# PWR_MCU.net
KiCad netlist of a schematic drawn in Altium Designer
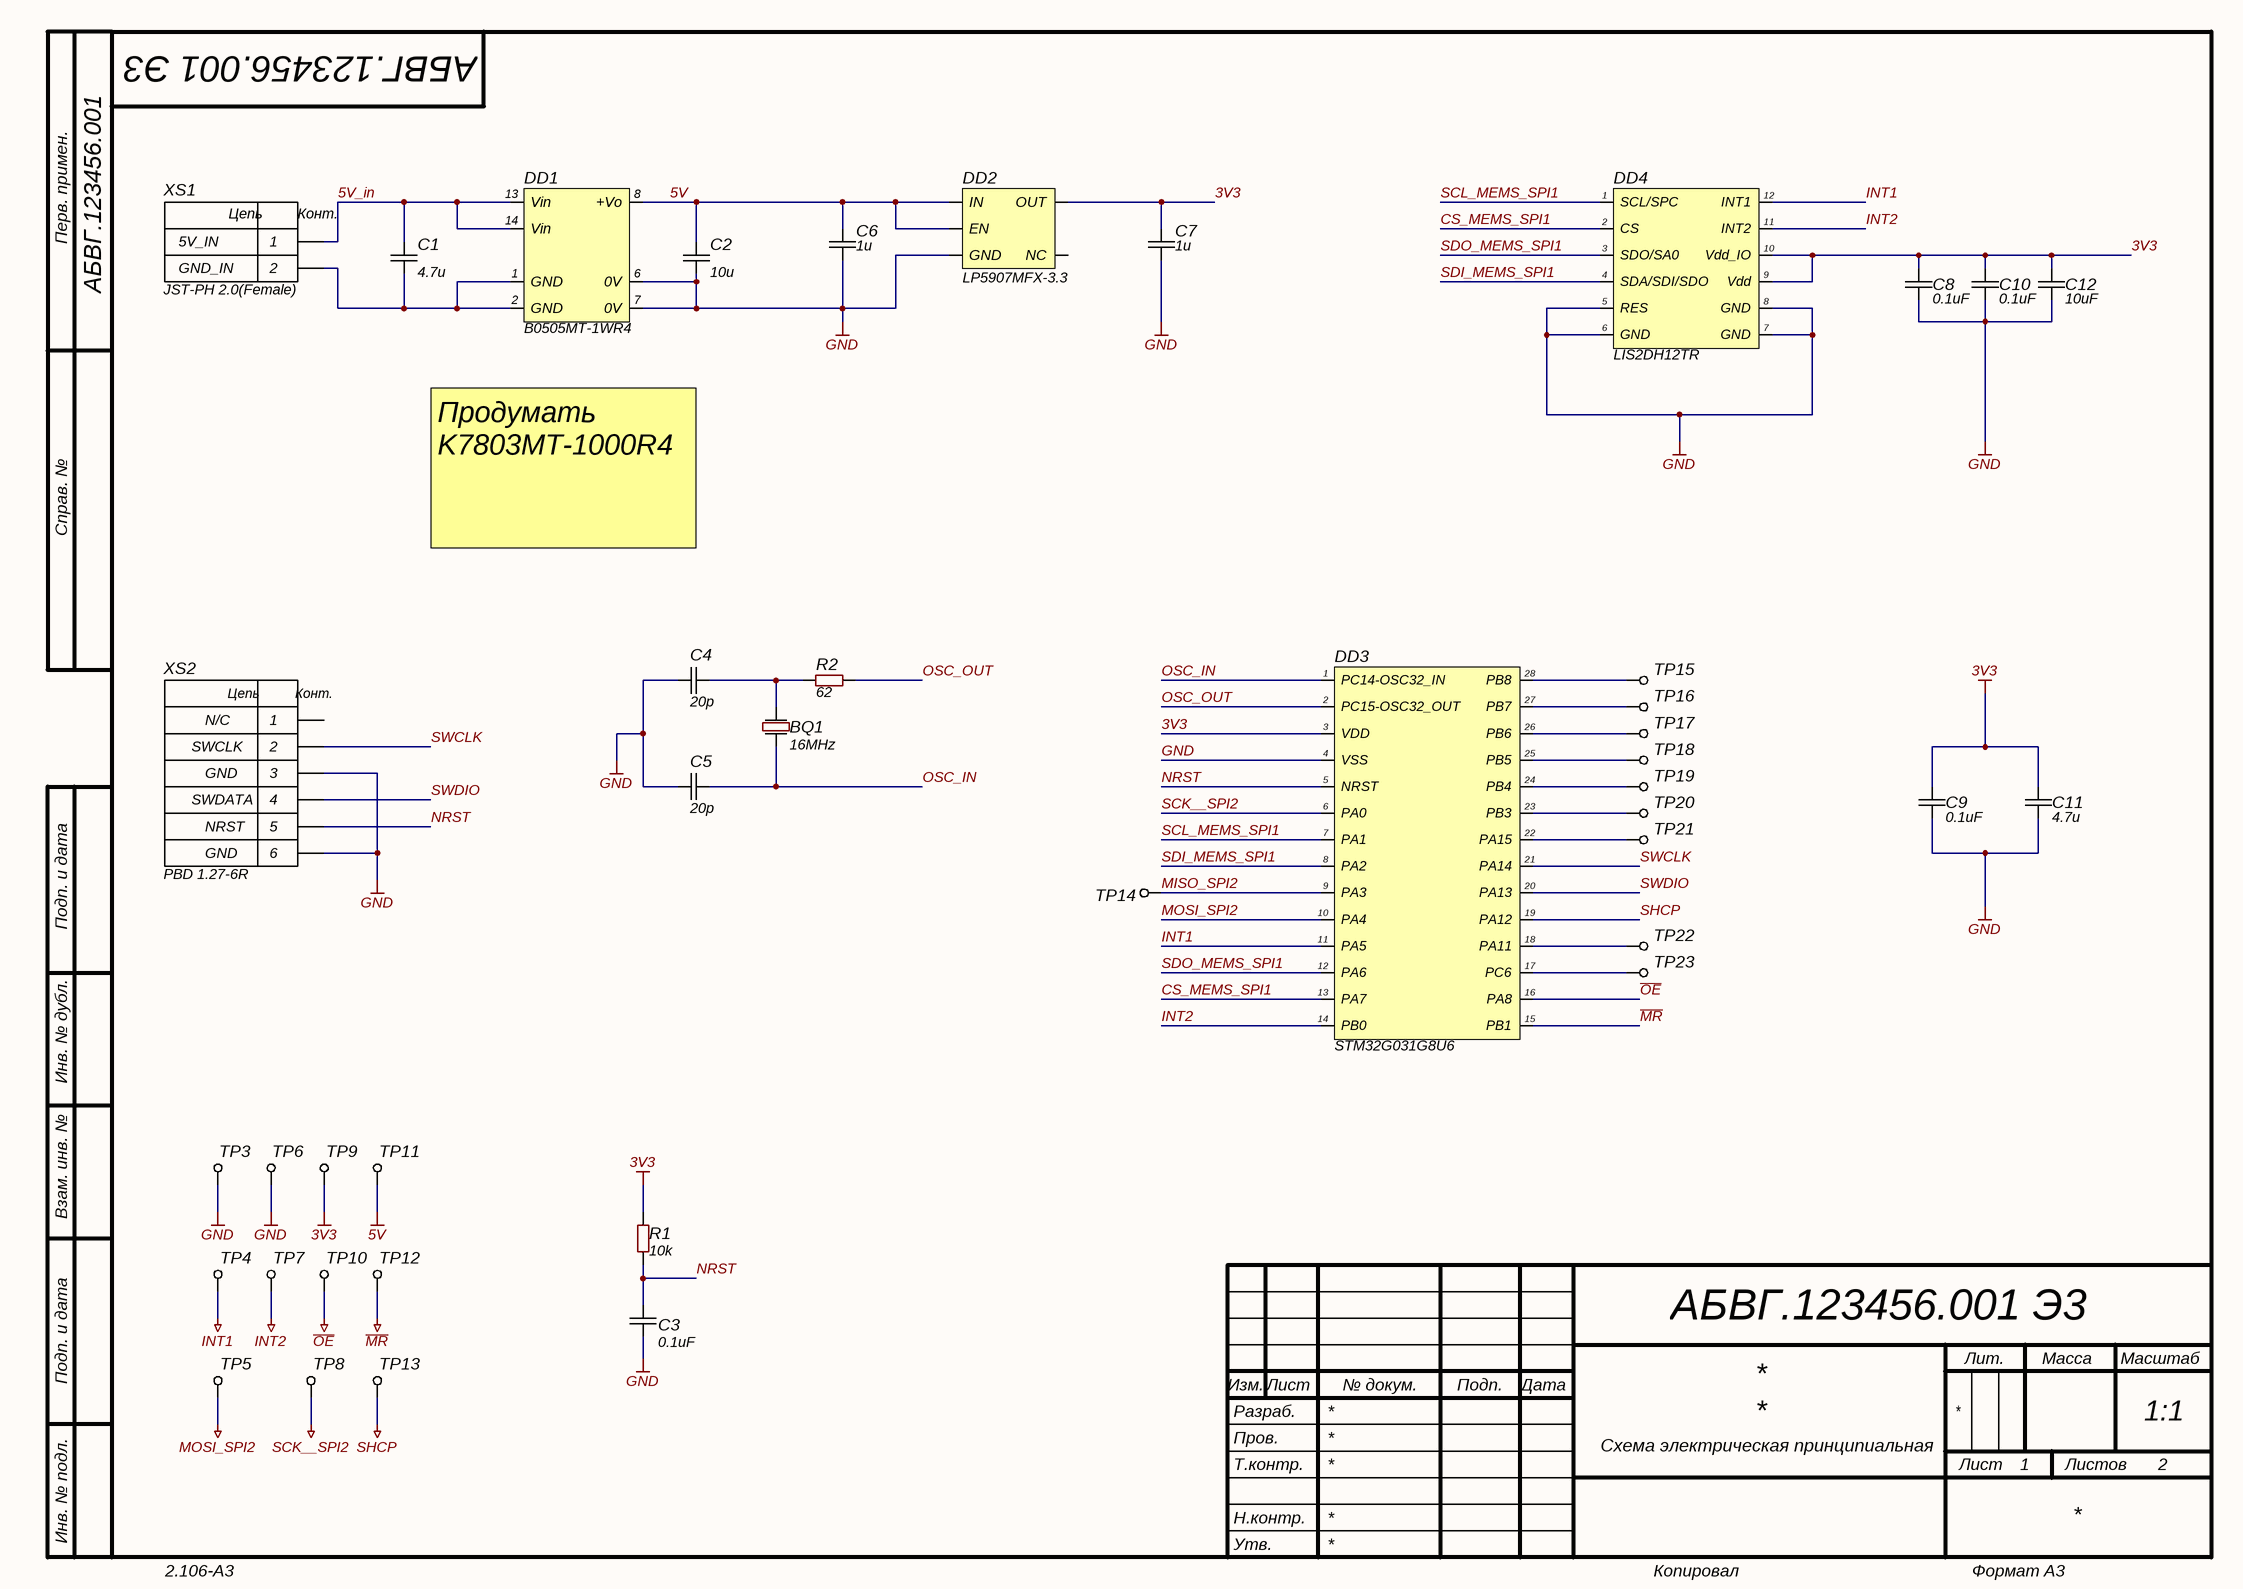
[diagram p0: PWR_MCU.SchDoc]

(export (version "E")
  (design (tool "Eeschema 10.0.6"))
  (components
    (comp (ref "BQ1")
      (value "SMD3225-16.000MHz")
      (footprint "OSC: 3225")
      (description "Resonator")
      (fields
        (field (name "MANUFACTURER") "Diodes Incorporated")
        (field (name "PARTNUMBER") "FL1000002")
        (field (name "FREQUENCY") "16MHz")
      )
      (libsource (lib "oscilator") (part "Crystal_3225"))
    )
    (comp (ref "C1")
      (value "4.7u")
      (footprint "CAP: 0805")
      (fields
        (field (name "MANUFACTURER") "Yageo")
        (field (name "PARTNUMBER") "CC0805KRX7R7BB104")
        (field (name "VALUEMANUFACTURERPARTNUMBER") "Ceramic capacitor, 4.7u, X7R, ±10%, 50V, 0805, -55...+125°C")
      )
      (libsource (lib "capacitor") (part "Ceramic_0805"))
    )
    (comp (ref "C2")
      (value "10u")
      (footprint "CAP: 0805")
      (fields
        (field (name "MANUFACTURER") "Yageo")
        (field (name "PARTNUMBER") "CC0805KRX7R7BB104")
        (field (name "VALUEMANUFACTURERPARTNUMBER") "Ceramic capacitor, 10u, X7R, ±10%, 50V, 0805, -55...+125°C")
      )
      (libsource (lib "capacitor") (part "Ceramic_0805"))
    )
    (comp (ref "C3")
      (value "0.1uF")
      (footprint "CAP: 0603")
      (fields
        (field (name "MANUFACTURER") "Yageo")
        (field (name "PARTNUMBER") "CC0603KRX7R7BB104")
        (field (name "VALUEMANUFACTURERPARTNUMBER") "Ceramic capacitor, 0.1uF, X7R, ±10%, 16V, 0603, -55...+125°C")
      )
      (libsource (lib "capacitor") (part "Ceramic_0603"))
    )
    (comp (ref "C4")
      (value "20p")
      (footprint "CAP: 0603")
      (description "Capacitor")
      (fields (field (name "MANUFACTURER") "Yageo") (field (name "PARTNUMBER") "CC0603KRX7R7BB104"))
      (libsource (lib "capacitor") (part "Ceramic_0603"))
    )
    (comp (ref "C5")
      (value "20p")
      (footprint "CAP: 0603")
      (description "Capacitor")
      (fields (field (name "MANUFACTURER") "Yageo") (field (name "PARTNUMBER") "CC0603KRX7R7BB104"))
      (libsource (lib "capacitor") (part "Ceramic_0603"))
    )
    (comp (ref "C6")
      (value "1u")
      (footprint "CAP: 0603")
      (description "Capacitor")
      (fields (field (name "MANUFACTURER") "Yageo") (field (name "PARTNUMBER") "CC0603KRX7R7BB104"))
      (libsource (lib "capacitor") (part "Ceramic_0603"))
    )
    (comp (ref "C7")
      (value "1u")
      (footprint "CAP: 0603")
      (description "Capacitor")
      (fields (field (name "MANUFACTURER") "Yageo") (field (name "PARTNUMBER") "CC0603KRX7R7BB104"))
      (libsource (lib "capacitor") (part "Ceramic_0603"))
    )
    (comp (ref "C8")
      (value "0.1uF")
      (footprint "CAP: 0603")
      (fields
        (field (name "MANUFACTURER") "Yageo")
        (field (name "PARTNUMBER") "CC0603KRX7R7BB104")
        (field (name "VALUEMANUFACTURERPARTNUMBER") "Ceramic capacitor, 0.1uF, X7R, ±10%, 16V, 0603, -55...+125°C")
      )
      (libsource (lib "capacitor") (part "Ceramic_0603"))
    )
    (comp (ref "C9")
      (value "0.1uF")
      (footprint "CAP: 0603")
      (fields
        (field (name "MANUFACTURER") "Yageo")
        (field (name "PARTNUMBER") "CC0603KRX7R7BB104")
        (field (name "VALUEMANUFACTURERPARTNUMBER") "Ceramic capacitor, 0.1uF, X7R, ±10%, 16V, 0603, -55...+125°C")
      )
      (libsource (lib "capacitor") (part "Ceramic_0603"))
    )
    (comp (ref "C10")
      (value "0.1uF")
      (footprint "CAP: 0603")
      (fields
        (field (name "MANUFACTURER") "Yageo")
        (field (name "PARTNUMBER") "CC0603KRX7R7BB104")
        (field (name "VALUEMANUFACTURERPARTNUMBER") "Ceramic capacitor, 0.1uF, X7R, ±10%, 16V, 0603, -55...+125°C")
      )
      (libsource (lib "capacitor") (part "Ceramic_0603"))
    )
    (comp (ref "C11")
      (value "4.7u")
      (footprint "CAP: 0603")
      (fields
        (field (name "MANUFACTURER") "Yageo")
        (field (name "PARTNUMBER") "CC0603KRX7R7BB104")
        (field (name "VALUEMANUFACTURERPARTNUMBER") "Ceramic capacitor, 4.7u, X7R, ±10%, 16V, 0603, -55...+125°C")
      )
      (libsource (lib "capacitor") (part "Ceramic_0603"))
    )
    (comp (ref "C12")
      (value "10uF")
      (footprint "CAP: 0603")
      (fields
        (field (name "MANUFACTURER") "Yageo")
        (field (name "PARTNUMBER") "CC0603KRX7R7BB104")
        (field (name "VALUEMANUFACTURERPARTNUMBER") "Ceramic capacitor, 10uF, X7R, ±10%, 16V, 0603, -55...+125°C")
      )
      (libsource (lib "capacitor") (part "Ceramic_0603"))
    )
    (comp (ref "DD1")
      (value "B0505MT-1WR4")
      (footprint "B0505MT-1WR4")
      (description "Isolated DC-DC converter")
      (libsource (lib "ic-power-supply") (part "B0505MT-1WR4"))
    )
    (comp (ref "DD2")
      (value "LP5907MFX-3.3")
      (footprint "SOT23-5")
      (description "LDO")
      (libsource (lib "ic-power-supply") (part "LP5907MFX-3.3"))
    )
    (comp (ref "DD3")
      (value "STM32G031G8U6")
      (footprint "28-UFQFPN")
      (description "Cortex-M0+")
      (libsource (lib "ic-mcu") (part "STM32G031G8U6"))
    )
    (comp (ref "DD4")
      (value "LIS2DH12TR")
      (footprint "12-LGA")
      (description "MEMS accelerometer")
      (libsource (lib "electromechanics") (part "LIS2DH12TR"))
    )
    (comp (ref "R1")
      (value "10k")
      (footprint "RES: 0603")
      (fields
        (field (name "MANUFACTURER") "Yageo")
        (field (name "PARTNUMBER") "RC0603JR-07100RL")
        (field (name "VALUEMANUFACTURERPARTNUMBER") "Resistor film, 10k, , 0603, 0.1W, -55...+125°C")
      )
      (libsource (lib "") (part "Resistor_0603_1"))
    )
    (comp (ref "R2")
      (value "62")
      (footprint "RES: 0603")
      (description "Resistor")
      (fields (field (name "MANUFACTURER") "Yageo") (field (name "PARTNUMBER") "RC0603JR-07100RL"))
      (libsource (lib "resistor") (part "Resistor_0603"))
    )
    (comp (ref "TP3")
      (value "Testpoint_HS1mm")
      (footprint "TestPoint(without hole)")
      (libsource (lib "connector") (part "Testpoint_HS1mm"))
    )
    (comp (ref "TP4")
      (value "Testpoint_HS1mm")
      (footprint "TestPoint(without hole)")
      (libsource (lib "connector") (part "Testpoint_HS1mm"))
    )
    (comp (ref "TP5")
      (value "Testpoint_HS1mm")
      (footprint "TestPoint(without hole)")
      (libsource (lib "connector") (part "Testpoint_HS1mm"))
    )
    (comp (ref "TP6")
      (value "Testpoint_HS1mm")
      (footprint "TestPoint(without hole)")
      (libsource (lib "connector") (part "Testpoint_HS1mm"))
    )
    (comp (ref "TP7")
      (value "Testpoint_HS1mm")
      (footprint "TestPoint(without hole)")
      (libsource (lib "connector") (part "Testpoint_HS1mm"))
    )
    (comp (ref "TP8")
      (value "Testpoint_HS1mm")
      (footprint "TestPoint(without hole)")
      (libsource (lib "connector") (part "Testpoint_HS1mm"))
    )
    (comp (ref "TP9")
      (value "Testpoint_HS1mm")
      (footprint "TestPoint(without hole)")
      (libsource (lib "connector") (part "Testpoint_HS1mm"))
    )
    (comp (ref "TP10")
      (value "Testpoint_HS1mm")
      (footprint "TestPoint(without hole)")
      (libsource (lib "connector") (part "Testpoint_HS1mm"))
    )
    (comp (ref "TP11")
      (value "Testpoint_HS1mm")
      (footprint "TestPoint(without hole)")
      (libsource (lib "connector") (part "Testpoint_HS1mm"))
    )
    (comp (ref "TP12")
      (value "Testpoint_HS1mm")
      (footprint "TestPoint(without hole)")
      (libsource (lib "connector") (part "Testpoint_HS1mm"))
    )
    (comp (ref "TP13")
      (value "Testpoint_HS1mm")
      (footprint "TestPoint(without hole)")
      (libsource (lib "connector") (part "Testpoint_HS1mm"))
    )
    (comp (ref "TP14")
      (value "Testpoint_HS1mm")
      (footprint "TestPoint(without hole)")
      (libsource (lib "connector") (part "Testpoint_HS1mm"))
    )
    (comp (ref "TP15")
      (value "Testpoint_HS1mm")
      (footprint "TestPoint(without hole)")
      (libsource (lib "connector") (part "Testpoint_HS1mm"))
    )
    (comp (ref "TP16")
      (value "Testpoint_HS1mm")
      (footprint "TestPoint(without hole)")
      (libsource (lib "connector") (part "Testpoint_HS1mm"))
    )
    (comp (ref "TP17")
      (value "Testpoint_HS1mm")
      (footprint "TestPoint(without hole)")
      (libsource (lib "connector") (part "Testpoint_HS1mm"))
    )
    (comp (ref "TP18")
      (value "Testpoint_HS1mm")
      (footprint "TestPoint(without hole)")
      (libsource (lib "connector") (part "Testpoint_HS1mm"))
    )
    (comp (ref "TP19")
      (value "Testpoint_HS1mm")
      (footprint "TestPoint(without hole)")
      (libsource (lib "connector") (part "Testpoint_HS1mm"))
    )
    (comp (ref "TP20")
      (value "Testpoint_HS1mm")
      (footprint "TestPoint(without hole)")
      (libsource (lib "connector") (part "Testpoint_HS1mm"))
    )
    (comp (ref "TP21")
      (value "Testpoint_HS1mm")
      (footprint "TestPoint(without hole)")
      (libsource (lib "connector") (part "Testpoint_HS1mm"))
    )
    (comp (ref "TP22")
      (value "Testpoint_HS1mm")
      (footprint "TestPoint(without hole)")
      (libsource (lib "connector") (part "Testpoint_HS1mm"))
    )
    (comp (ref "TP23")
      (value "Testpoint_HS1mm")
      (footprint "TestPoint(without hole)")
      (libsource (lib "connector") (part "Testpoint_HS1mm"))
    )
    (comp (ref "XS1")
      (value "JST-PH 2.0(Female)")
      (footprint "JST-PH 2.0(Female)")
      (libsource (lib "connector") (part "JST-PH 2.0(Female)"))
    )
    (comp (ref "XS2")
      (value "PBD 1.27-6R")
      (footprint "CON: PLLD-6R(1.27)")
      (description "DS1065-14-2X3S8BR")
      (libsource (lib "connector") (part "PBD 1.27-6R"))
    )
  )
  (nets
    (net (code "1") (name "/5V_in") (class "Default")
      (node (ref "C1") (pin "2") (pinfunction "2_2") (pintype "passive"))
      (node (ref "DD1") (pin "13") (pinfunction "Vin_13") (pintype "passive"))
      (node (ref "DD1") (pin "14") (pinfunction "Vin_14") (pintype "passive"))
      (node (ref "XS1") (pin "1") (pinfunction "1_1") (pintype "passive"))
    )
    (net (code "2") (name "/CS_MEMS_SPI1") (class "Default")
      (node (ref "DD3") (pin "13") (pinfunction "PA7_13") (pintype "passive"))
      (node (ref "DD4") (pin "2") (pinfunction "CS_2") (pintype "passive"))
    )
    (net (code "3") (name "/MISO_SPI2") (class "Default")
      (node (ref "DD3") (pin "9") (pinfunction "PA3_9") (pintype "passive"))
      (node (ref "TP14") (pin "1") (pinfunction "1_1") (pintype "passive"))
    )
    (net (code "4") (name "/NRST") (class "Default")
      (node (ref "C3") (pin "2") (pinfunction "2_2") (pintype "passive"))
      (node (ref "DD3") (pin "5") (pinfunction "NRST_5") (pintype "passive"))
      (node (ref "R1") (pin "1") (pinfunction "1_1") (pintype "passive"))
      (node (ref "XS2") (pin "5") (pinfunction "5_5") (pintype "passive"))
    )
    (net (code "5") (name "/OSC_IN") (class "Default")
      (node (ref "BQ1") (pin "1") (pinfunction "1_1") (pintype "passive"))
      (node (ref "C5") (pin "1") (pinfunction "1_1") (pintype "passive"))
      (node (ref "DD3") (pin "1") (pinfunction "PC14-OSC32_IN_1") (pintype "passive"))
    )
    (net (code "6") (name "/OSC_OUT") (class "Default")
      (node (ref "DD3") (pin "2") (pinfunction "PC15-OSC32_OUT_2") (pintype "passive"))
      (node (ref "R2") (pin "1") (pinfunction "1_1") (pintype "passive"))
    )
    (net (code "7") (name "/SCL_MEMS_SPI1") (class "Default")
      (node (ref "DD3") (pin "7") (pinfunction "PA1_7") (pintype "passive"))
      (node (ref "DD4") (pin "1") (pinfunction "SCL/SPC_1") (pintype "passive"))
    )
    (net (code "8") (name "/SDI_MEMS_SPI1") (class "Default")
      (node (ref "DD3") (pin "8") (pinfunction "PA2_8") (pintype "passive"))
      (node (ref "DD4") (pin "4") (pinfunction "SDA/SDI/SDO_4") (pintype "passive"))
    )
    (net (code "9") (name "/SDO_MEMS_SPI1") (class "Default")
      (node (ref "DD3") (pin "12") (pinfunction "PA6_12") (pintype "passive"))
      (node (ref "DD4") (pin "3") (pinfunction "SDO/SA0_3") (pintype "passive"))
    )
    (net (code "10") (name "/SWCLK") (class "Default")
      (node (ref "DD3") (pin "21") (pinfunction "PA14_21") (pintype "passive"))
      (node (ref "XS2") (pin "2") (pinfunction "2_2") (pintype "passive"))
    )
    (net (code "11") (name "/SWDIO") (class "Default")
      (node (ref "DD3") (pin "20") (pinfunction "PA13_20") (pintype "passive"))
      (node (ref "XS2") (pin "4") (pinfunction "4_4") (pintype "passive"))
    )
    (net (code "12") (name "3V3") (class "Default")
      (node (ref "C10") (pin "2") (pinfunction "2_2") (pintype "passive"))
      (node (ref "C11") (pin "2") (pinfunction "2_2") (pintype "passive"))
      (node (ref "C12") (pin "2") (pinfunction "2_2") (pintype "passive"))
      (node (ref "C7") (pin "2") (pinfunction "2_2") (pintype "passive"))
      (node (ref "C8") (pin "2") (pinfunction "2_2") (pintype "passive"))
      (node (ref "C9") (pin "2") (pinfunction "2_2") (pintype "passive"))
      (node (ref "DD2") (pin "5") (pinfunction "OUT_5") (pintype "passive"))
      (node (ref "DD3") (pin "3") (pinfunction "VDD_3") (pintype "passive"))
      (node (ref "DD4") (pin "10") (pinfunction "Vdd_IO_10") (pintype "passive"))
      (node (ref "DD4") (pin "9") (pinfunction "Vdd_9") (pintype "passive"))
      (node (ref "R1") (pin "2") (pinfunction "2_2") (pintype "passive"))
      (node (ref "TP9") (pin "1") (pinfunction "1_1") (pintype "passive"))
    )
    (net (code "13") (name "5V") (class "Default")
      (node (ref "C2") (pin "2") (pinfunction "2_2") (pintype "passive"))
      (node (ref "C6") (pin "2") (pinfunction "2_2") (pintype "passive"))
      (node (ref "DD1") (pin "8") (pinfunction "+Vo_8") (pintype "passive"))
      (node (ref "DD2") (pin "1") (pinfunction "IN_1") (pintype "passive"))
      (node (ref "DD2") (pin "3") (pinfunction "EN_3") (pintype "passive"))
      (node (ref "TP11") (pin "1") (pinfunction "1_1") (pintype "passive"))
    )
    (net (code "14") (name "GND") (class "Default")
      (node (ref "C10") (pin "1") (pinfunction "1_1") (pintype "passive"))
      (node (ref "C11") (pin "1") (pinfunction "1_1") (pintype "passive"))
      (node (ref "C12") (pin "1") (pinfunction "1_1") (pintype "passive"))
      (node (ref "C2") (pin "1") (pinfunction "1_1") (pintype "passive"))
      (node (ref "C3") (pin "1") (pinfunction "1_1") (pintype "passive"))
      (node (ref "C4") (pin "2") (pinfunction "2_2") (pintype "passive"))
      (node (ref "C5") (pin "2") (pinfunction "2_2") (pintype "passive"))
      (node (ref "C6") (pin "1") (pinfunction "1_1") (pintype "passive"))
      (node (ref "C7") (pin "1") (pinfunction "1_1") (pintype "passive"))
      (node (ref "C8") (pin "1") (pinfunction "1_1") (pintype "passive"))
      (node (ref "C9") (pin "1") (pinfunction "1_1") (pintype "passive"))
      (node (ref "DD1") (pin "6") (pinfunction "0V_6") (pintype "passive"))
      (node (ref "DD1") (pin "7") (pinfunction "0V_7") (pintype "passive"))
      (node (ref "DD2") (pin "2") (pinfunction "GND_2") (pintype "passive"))
      (node (ref "DD3") (pin "4") (pinfunction "VSS_4") (pintype "passive"))
      (node (ref "DD4") (pin "5") (pinfunction "RES_5") (pintype "passive"))
      (node (ref "DD4") (pin "6") (pinfunction "GND_6") (pintype "passive"))
      (node (ref "DD4") (pin "7") (pinfunction "GND_7") (pintype "passive"))
      (node (ref "DD4") (pin "8") (pinfunction "GND_8") (pintype "passive"))
      (node (ref "TP3") (pin "1") (pinfunction "1_1") (pintype "passive"))
      (node (ref "TP6") (pin "1") (pinfunction "1_1") (pintype "passive"))
      (node (ref "XS2") (pin "3") (pinfunction "3_3") (pintype "passive"))
      (node (ref "XS2") (pin "6") (pinfunction "6_6") (pintype "passive"))
    )
    (net (code "15") (name "INT1") (class "Default")
      (node (ref "DD3") (pin "11") (pinfunction "PA5_11") (pintype "passive"))
      (node (ref "DD4") (pin "12") (pinfunction "INT1_12") (pintype "passive"))
      (node (ref "TP4") (pin "1") (pinfunction "1_1") (pintype "passive"))
    )
    (net (code "16") (name "INT2") (class "Default")
      (node (ref "DD3") (pin "14") (pinfunction "PB0_14") (pintype "passive"))
      (node (ref "DD4") (pin "11") (pinfunction "INT2_11") (pintype "passive"))
      (node (ref "TP7") (pin "1") (pinfunction "1_1") (pintype "passive"))
    )
    (net (code "17") (name "MOSI_SPI2") (class "Default")
      (node (ref "DD3") (pin "10") (pinfunction "PA4_10") (pintype "passive"))
      (node (ref "TP5") (pin "1") (pinfunction "1_1") (pintype "passive"))
    )
    (net (code "18") (name "Net-(BQ1-Pad3)") (class "Default")
      (node (ref "BQ1") (pin "3") (pinfunction "3_3") (pintype "passive"))
      (node (ref "C4") (pin "1") (pinfunction "1_1") (pintype "passive"))
      (node (ref "R2") (pin "2") (pinfunction "2_2") (pintype "passive"))
    )
    (net (code "19") (name "Net-(C1-Pad1)") (class "Default")
      (node (ref "C1") (pin "1") (pinfunction "1_1") (pintype "passive"))
      (node (ref "DD1") (pin "1") (pinfunction "GND_1") (pintype "passive"))
      (node (ref "DD1") (pin "2") (pinfunction "GND_2") (pintype "passive"))
      (node (ref "XS1") (pin "2") (pinfunction "2_2") (pintype "passive"))
    )
    (net (code "20") (name "Net-(DD3-PA11)") (class "Default")
      (node (ref "DD3") (pin "18") (pinfunction "PA11_18") (pintype "passive"))
      (node (ref "TP22") (pin "1") (pinfunction "1_1") (pintype "passive"))
    )
    (net (code "21") (name "Net-(DD3-PA15)") (class "Default")
      (node (ref "DD3") (pin "22") (pinfunction "PA15_22") (pintype "passive"))
      (node (ref "TP21") (pin "1") (pinfunction "1_1") (pintype "passive"))
    )
    (net (code "22") (name "Net-(DD3-PB3)") (class "Default")
      (node (ref "DD3") (pin "23") (pinfunction "PB3_23") (pintype "passive"))
      (node (ref "TP20") (pin "1") (pinfunction "1_1") (pintype "passive"))
    )
    (net (code "23") (name "Net-(DD3-PB4)") (class "Default")
      (node (ref "DD3") (pin "24") (pinfunction "PB4_24") (pintype "passive"))
      (node (ref "TP19") (pin "1") (pinfunction "1_1") (pintype "passive"))
    )
    (net (code "24") (name "Net-(DD3-PB5)") (class "Default")
      (node (ref "DD3") (pin "25") (pinfunction "PB5_25") (pintype "passive"))
      (node (ref "TP18") (pin "1") (pinfunction "1_1") (pintype "passive"))
    )
    (net (code "25") (name "Net-(DD3-PB6)") (class "Default")
      (node (ref "DD3") (pin "26") (pinfunction "PB6_26") (pintype "passive"))
      (node (ref "TP17") (pin "1") (pinfunction "1_1") (pintype "passive"))
    )
    (net (code "26") (name "Net-(DD3-PB7)") (class "Default")
      (node (ref "DD3") (pin "27") (pinfunction "PB7_27") (pintype "passive"))
      (node (ref "TP16") (pin "1") (pinfunction "1_1") (pintype "passive"))
    )
    (net (code "27") (name "Net-(DD3-PB8)") (class "Default")
      (node (ref "DD3") (pin "28") (pinfunction "PB8_28") (pintype "passive"))
      (node (ref "TP15") (pin "1") (pinfunction "1_1") (pintype "passive"))
    )
    (net (code "28") (name "Net-(DD3-PC6)") (class "Default")
      (node (ref "DD3") (pin "17") (pinfunction "PC6_17") (pintype "passive"))
      (node (ref "TP23") (pin "1") (pinfunction "1_1") (pintype "passive"))
    )
    (net (code "29") (name "SCK__SPI2") (class "Default")
      (node (ref "DD3") (pin "6") (pinfunction "PA0_6") (pintype "passive"))
      (node (ref "TP8") (pin "1") (pinfunction "1_1") (pintype "passive"))
    )
    (net (code "30") (name "SHCP") (class "Default")
      (node (ref "DD3") (pin "19") (pinfunction "PA12_19") (pintype "passive"))
      (node (ref "TP13") (pin "1") (pinfunction "1_1") (pintype "passive"))
    )
    (net (code "31") (name "unconnected-(DD2-NC-Pad4)") (class "Default")
      (node (ref "DD2") (pin "4") (pinfunction "NC_4") (pintype "passive"))
    )
    (net (code "32") (name "unconnected-(XS2-Pad1)") (class "Default")
      (node (ref "XS2") (pin "1") (pinfunction "1_1") (pintype "passive"))
    )
    (net (code "33") (name "~{MR}") (class "Default")
      (node (ref "DD3") (pin "15") (pinfunction "PB1_15") (pintype "passive"))
      (node (ref "TP12") (pin "1") (pinfunction "1_1") (pintype "passive"))
    )
    (net (code "34") (name "~{OE}") (class "Default")
      (node (ref "DD3") (pin "16") (pinfunction "PA8_16") (pintype "passive"))
      (node (ref "TP10") (pin "1") (pinfunction "1_1") (pintype "passive"))
    )
  )
)
